# schematic.net
KiCad netlist of a schematic drawn in EAGLE
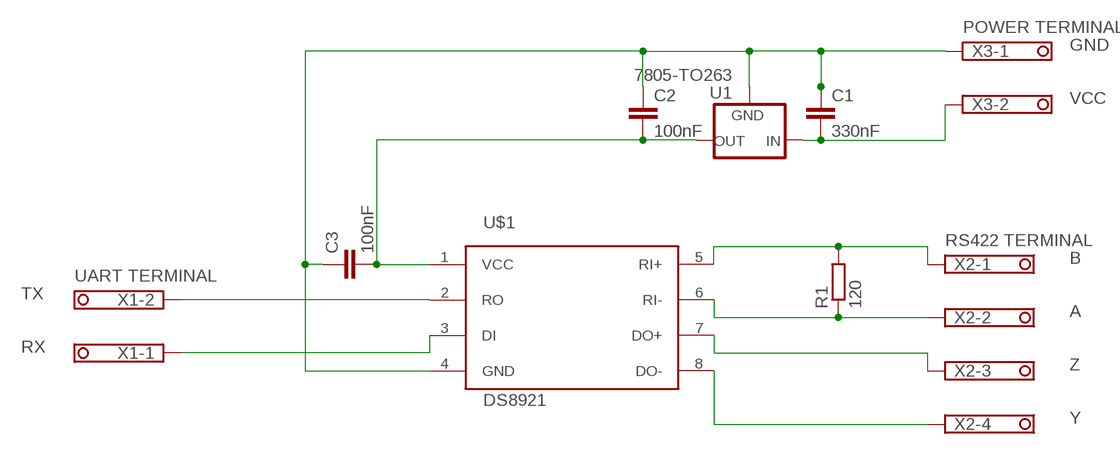
[diagram p0: schematic, sheet 1]

(export (version "E")
  (design (tool "Eeschema 10.0.6"))
  (components
    (comp (ref "C1")
      (value "330nF")
      (footprint "eagle-import:C1206K")
      (libsource (lib "eagle-import") (part "C-EUC1206K"))
    )
    (comp (ref "C2")
      (value "100nF")
      (footprint "eagle-import:C1206K")
      (libsource (lib "eagle-import") (part "C-EUC1206K"))
    )
    (comp (ref "C3")
      (value "100nF")
      (footprint "eagle-import:C1206K")
      (libsource (lib "eagle-import") (part "C-EUC1206K"))
    )
    (comp (ref "R1")
      (value "120")
      (footprint "eagle-import:R1206")
      (libsource (lib "eagle-import") (part "R-EU_R1206"))
    )
    (comp (ref "U$1")
      (value "DS8921")
      (footprint "eagle-import:SOIC8")
      (libsource (lib "eagle-import") (part "DS8921"))
    )
    (comp (ref "U1")
      (value "7805-TO263")
      (footprint "eagle-import:D2PAK")
      (libsource (lib "eagle-import") (part "L78XXD2TT"))
    )
    (comp (ref "X1")
      (value "1751248")
      (footprint "eagle-import:1751248")
      (libsource (lib "eagle-import") (part "1751248"))
    )
    (comp (ref "X2")
      (value "1751264")
      (footprint "eagle-import:1751264")
      (libsource (lib "eagle-import") (part "1751264"))
    )
    (comp (ref "X3")
      (value "1751248")
      (footprint "eagle-import:1751248")
      (libsource (lib "eagle-import") (part "1751248"))
    )
  )
  (nets
    (net (code "1") (name "Net-(U$1-DI)") (class "Default")
      (node (ref "U$1") (pin "3") (pinfunction "DI_3") (pintype "bidirectional"))
      (node (ref "X1") (pin "1") (pinfunction "K_1") (pintype "passive"))
    )
    (net (code "2") (name "Net-(U$1-DO+)") (class "Default")
      (node (ref "U$1") (pin "7") (pinfunction "DO+_7") (pintype "bidirectional"))
      (node (ref "X2") (pin "3") (pinfunction "K_3") (pintype "passive"))
    )
    (net (code "3") (name "Net-(U$1-DO-)") (class "Default")
      (node (ref "U$1") (pin "8") (pinfunction "DO-_8") (pintype "bidirectional"))
      (node (ref "X2") (pin "4") (pinfunction "K_4") (pintype "passive"))
    )
    (net (code "4") (name "Net-(U$1-GND)") (class "Default")
      (node (ref "C1") (pin "1") (pinfunction "1_1") (pintype "passive"))
      (node (ref "C2") (pin "1") (pinfunction "1_1") (pintype "passive"))
      (node (ref "C3") (pin "1") (pinfunction "1_1") (pintype "passive"))
      (node (ref "U$1") (pin "4") (pinfunction "GND_4") (pintype "bidirectional"))
      (node (ref "U1") (pin "2") (pinfunction "GND_2") (pintype "input"))
      (node (ref "X3") (pin "1") (pinfunction "K_1") (pintype "passive"))
    )
    (net (code "5") (name "Net-(U$1-RI+)") (class "Default")
      (node (ref "R1") (pin "2") (pinfunction "2_2") (pintype "passive"))
      (node (ref "U$1") (pin "5") (pinfunction "RI+_5") (pintype "bidirectional"))
      (node (ref "X2") (pin "1") (pinfunction "K_1") (pintype "passive"))
    )
    (net (code "6") (name "Net-(U$1-RI-)") (class "Default")
      (node (ref "R1") (pin "1") (pinfunction "1_1") (pintype "passive"))
      (node (ref "U$1") (pin "6") (pinfunction "RI-_6") (pintype "bidirectional"))
      (node (ref "X2") (pin "2") (pinfunction "K_2") (pintype "passive"))
    )
    (net (code "7") (name "Net-(U$1-RO)") (class "Default")
      (node (ref "U$1") (pin "2") (pinfunction "RO_2") (pintype "bidirectional"))
      (node (ref "X1") (pin "2") (pinfunction "K_2") (pintype "passive"))
    )
    (net (code "8") (name "Net-(U$1-VCC)") (class "Default")
      (node (ref "C2") (pin "2") (pinfunction "2_2") (pintype "passive"))
      (node (ref "C3") (pin "2") (pinfunction "2_2") (pintype "passive"))
      (node (ref "U$1") (pin "1") (pinfunction "VCC_1") (pintype "bidirectional"))
      (node (ref "U1") (pin "3") (pinfunction "OUT_3") (pintype "passive"))
    )
    (net (code "9") (name "Net-(U1-IN)") (class "Default")
      (node (ref "C1") (pin "2") (pinfunction "2_2") (pintype "passive"))
      (node (ref "U1") (pin "1") (pinfunction "IN_1") (pintype "input"))
      (node (ref "X3") (pin "2") (pinfunction "K_2") (pintype "passive"))
    )
  )
)
